# oven-controller-v1.net
KiCad netlist of a schematic drawn in EAGLE
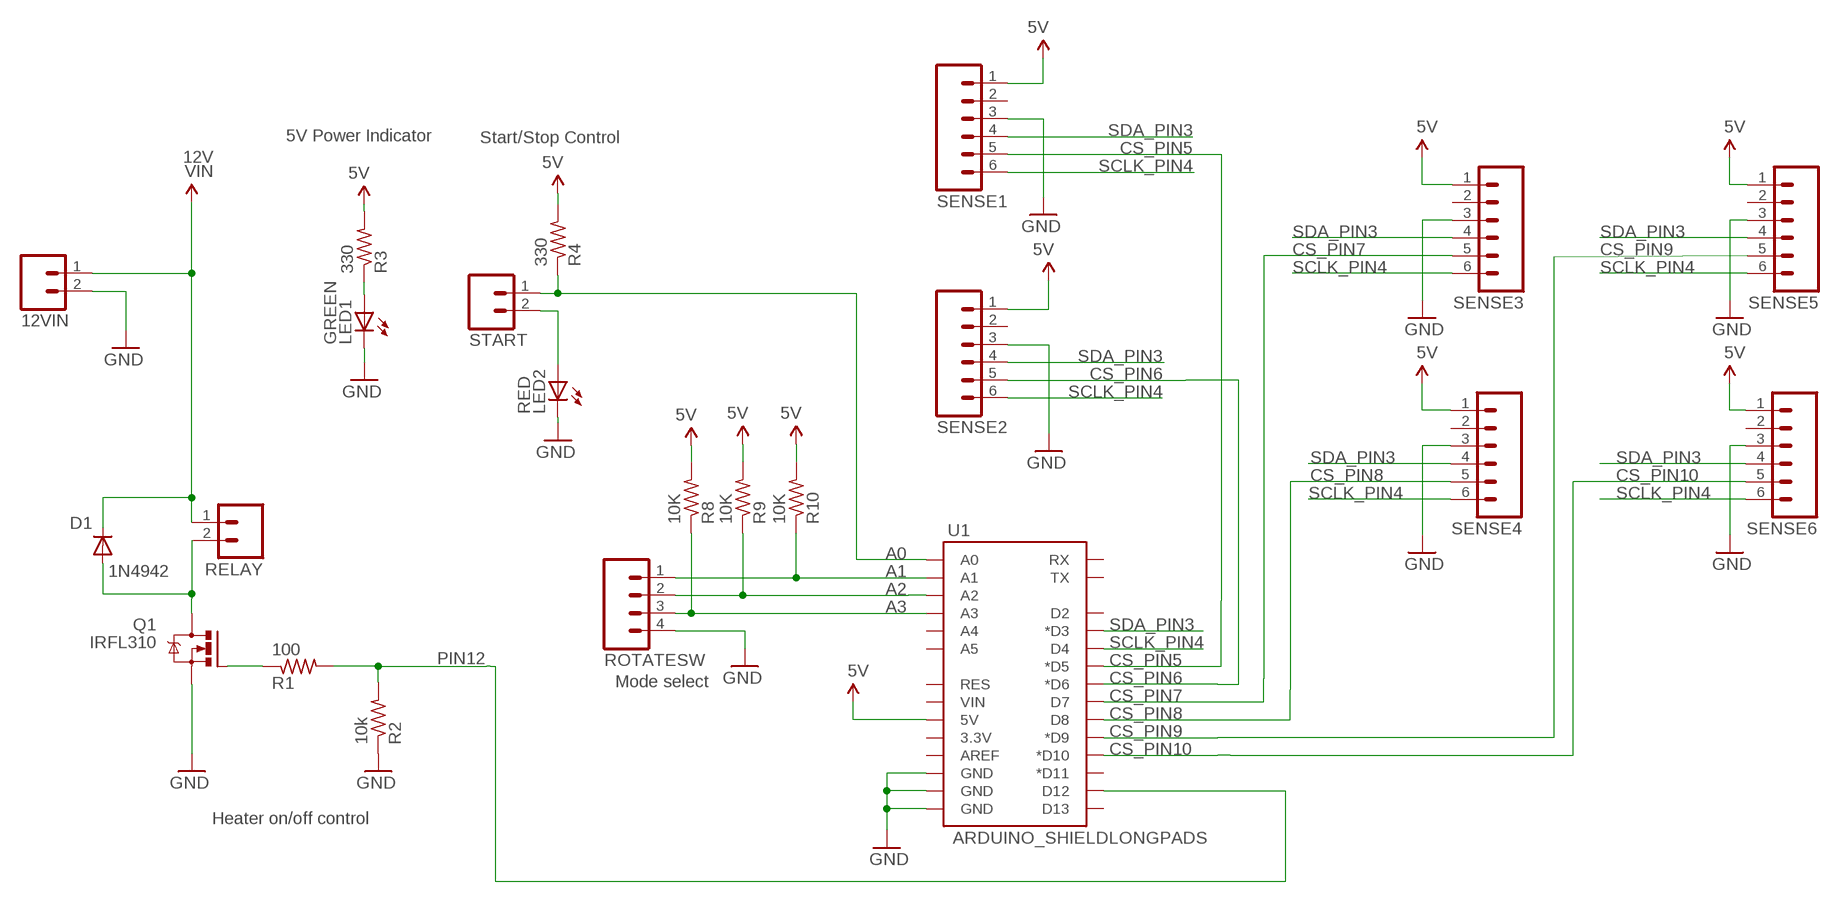
[diagram p0: schematic, sheet 1]

(export (version "E")
  (design (tool "Eeschema 10.0.6"))
  (components
    (comp (ref "12VIN")
      (value "M023.5MM_LOCK")
      (footprint "eagle-import:SCREWTERMINAL-3.5MM-2_LOCK")
      (libsource (lib "eagle-import") (part "M023.5MM_LOCK"))
    )
    (comp (ref "D1")
      (value "1N4942")
      (footprint "eagle-import:DO41-10")
      (libsource (lib "eagle-import") (part "1N4942"))
    )
    (comp (ref "LED1")
      (value "GREEN")
      (footprint "eagle-import:LED5MM")
      (libsource (lib "eagle-import") (part "LED5MM"))
    )
    (comp (ref "LED2")
      (value "RED")
      (footprint "eagle-import:LED5MM")
      (libsource (lib "eagle-import") (part "LED5MM"))
    )
    (comp (ref "Q1")
      (value "IRFL310")
      (footprint "eagle-import:TO220BV")
      (libsource (lib "eagle-import") (part "IRF520"))
    )
    (comp (ref "R1")
      (value "100")
      (footprint "eagle-import:V234_12")
      (libsource (lib "eagle-import") (part "R-US_V234/12"))
    )
    (comp (ref "R2")
      (value "10k")
      (footprint "eagle-import:V234_12")
      (libsource (lib "eagle-import") (part "R-US_V234/12"))
    )
    (comp (ref "R3")
      (value "330")
      (footprint "eagle-import:0207_10")
      (libsource (lib "eagle-import") (part "R-US_0207/10"))
    )
    (comp (ref "R4")
      (value "330")
      (footprint "eagle-import:0207_10")
      (libsource (lib "eagle-import") (part "R-US_0207/10"))
    )
    (comp (ref "R8")
      (value "10K")
      (footprint "eagle-import:0207_10")
      (libsource (lib "eagle-import") (part "R-US_0207/10"))
    )
    (comp (ref "R9")
      (value "10K")
      (footprint "eagle-import:0207_10")
      (libsource (lib "eagle-import") (part "R-US_0207/10"))
    )
    (comp (ref "R10")
      (value "10K")
      (footprint "eagle-import:0207_10")
      (libsource (lib "eagle-import") (part "R-US_0207/10"))
    )
    (comp (ref "RELAY")
      (value "M023.5MM_LOCK")
      (footprint "eagle-import:SCREWTERMINAL-3.5MM-2_LOCK")
      (libsource (lib "eagle-import") (part "M023.5MM_LOCK"))
    )
    (comp (ref "ROTATESW")
      (value "M04LOCK_LONGPADS")
      (footprint "eagle-import:1X04_LOCK_LONGPADS")
      (libsource (lib "eagle-import") (part "M04LOCK_LONGPADS"))
    )
    (comp (ref "SENSE1")
      (value "M06LOCK_LONGPADS")
      (footprint "eagle-import:1X06_LOCK_LONGPADS")
      (libsource (lib "eagle-import") (part "M06LOCK_LONGPADS"))
    )
    (comp (ref "SENSE2")
      (value "M06LOCK_LONGPADS")
      (footprint "eagle-import:1X06_LOCK_LONGPADS")
      (libsource (lib "eagle-import") (part "M06LOCK_LONGPADS"))
    )
    (comp (ref "SENSE3")
      (value "M06LOCK_LONGPADS")
      (footprint "eagle-import:1X06_LOCK_LONGPADS")
      (libsource (lib "eagle-import") (part "M06LOCK_LONGPADS"))
    )
    (comp (ref "SENSE4")
      (value "M06LOCK_LONGPADS")
      (footprint "eagle-import:1X06_LOCK_LONGPADS")
      (libsource (lib "eagle-import") (part "M06LOCK_LONGPADS"))
    )
    (comp (ref "SENSE5")
      (value "M06LOCK_LONGPADS")
      (footprint "eagle-import:1X06_LOCK_LONGPADS")
      (libsource (lib "eagle-import") (part "M06LOCK_LONGPADS"))
    )
    (comp (ref "SENSE6")
      (value "M06LOCK_LONGPADS")
      (footprint "eagle-import:1X06_LOCK_LONGPADS")
      (libsource (lib "eagle-import") (part "M06LOCK_LONGPADS"))
    )
    (comp (ref "START")
      (value "M023.5MM_LOCK")
      (footprint "eagle-import:SCREWTERMINAL-3.5MM-2_LOCK")
      (libsource (lib "eagle-import") (part "M023.5MM_LOCK"))
    )
    (comp (ref "U1")
      (value "ARDUINO_SHIELDLONGPADS")
      (footprint "eagle-import:DUEMILANOVE_SHIELD_LONGPADS")
      (libsource (lib "eagle-import") (part "ARDUINO_SHIELDLONGPADS"))
    )
  )
  (nets
    (net (code "1") (name "/A0") (class "Default")
      (node (ref "R4") (pin "1") (pinfunction "1_1") (pintype "passive"))
      (node (ref "START") (pin "1") (pinfunction "1_1") (pintype "passive"))
      (node (ref "U1") (pin "A0") (pinfunction "A0_A0") (pintype "bidirectional"))
    )
    (net (code "2") (name "/A1") (class "Default")
      (node (ref "R10") (pin "1") (pinfunction "1_1") (pintype "passive"))
      (node (ref "ROTATESW") (pin "1") (pinfunction "1_1") (pintype "passive"))
      (node (ref "U1") (pin "A1") (pinfunction "A1_A1") (pintype "bidirectional"))
    )
    (net (code "3") (name "/A2") (class "Default")
      (node (ref "R9") (pin "1") (pinfunction "1_1") (pintype "passive"))
      (node (ref "ROTATESW") (pin "2") (pinfunction "2_2") (pintype "passive"))
      (node (ref "U1") (pin "A2") (pinfunction "A2_A2") (pintype "bidirectional"))
    )
    (net (code "4") (name "/A3") (class "Default")
      (node (ref "R8") (pin "1") (pinfunction "1_1") (pintype "passive"))
      (node (ref "ROTATESW") (pin "3") (pinfunction "3_3") (pintype "passive"))
      (node (ref "U1") (pin "A3") (pinfunction "A3_A3") (pintype "bidirectional"))
    )
    (net (code "5") (name "/CS_PIN5") (class "Default")
      (node (ref "SENSE1") (pin "5") (pinfunction "5_5") (pintype "passive"))
      (node (ref "U1") (pin "D5") (pinfunction "*D5_D5") (pintype "bidirectional"))
    )
    (net (code "6") (name "/CS_PIN6") (class "Default")
      (node (ref "SENSE2") (pin "5") (pinfunction "5_5") (pintype "passive"))
      (node (ref "U1") (pin "D6") (pinfunction "*D6_D6") (pintype "bidirectional"))
    )
    (net (code "7") (name "/CS_PIN7") (class "Default")
      (node (ref "SENSE3") (pin "5") (pinfunction "5_5") (pintype "passive"))
      (node (ref "U1") (pin "D7") (pinfunction "D7_D7") (pintype "bidirectional"))
    )
    (net (code "8") (name "/CS_PIN8") (class "Default")
      (node (ref "SENSE4") (pin "5") (pinfunction "5_5") (pintype "passive"))
      (node (ref "U1") (pin "D8") (pinfunction "D8_D8") (pintype "bidirectional"))
    )
    (net (code "9") (name "/CS_PIN9") (class "Default")
      (node (ref "SENSE5") (pin "5") (pinfunction "5_5") (pintype "passive"))
      (node (ref "U1") (pin "D9") (pinfunction "*D9_D9") (pintype "bidirectional"))
    )
    (net (code "10") (name "/CS_PIN10") (class "Default")
      (node (ref "SENSE6") (pin "5") (pinfunction "5_5") (pintype "passive"))
      (node (ref "U1") (pin "D10") (pinfunction "*D10_D10") (pintype "bidirectional"))
    )
    (net (code "11") (name "/PIN12") (class "Default")
      (node (ref "R1") (pin "2") (pinfunction "2_2") (pintype "passive"))
      (node (ref "R2") (pin "2") (pinfunction "2_2") (pintype "passive"))
      (node (ref "U1") (pin "D12") (pinfunction "D12_D12") (pintype "bidirectional"))
    )
    (net (code "12") (name "/SCLK_PIN4") (class "Default")
      (node (ref "SENSE1") (pin "6") (pinfunction "6_6") (pintype "passive"))
      (node (ref "SENSE2") (pin "6") (pinfunction "6_6") (pintype "passive"))
      (node (ref "SENSE3") (pin "6") (pinfunction "6_6") (pintype "passive"))
      (node (ref "SENSE4") (pin "6") (pinfunction "6_6") (pintype "passive"))
      (node (ref "SENSE5") (pin "6") (pinfunction "6_6") (pintype "passive"))
      (node (ref "SENSE6") (pin "6") (pinfunction "6_6") (pintype "passive"))
      (node (ref "U1") (pin "D4") (pinfunction "D4_D4") (pintype "bidirectional"))
    )
    (net (code "13") (name "/SDA_PIN3") (class "Default")
      (node (ref "SENSE1") (pin "4") (pinfunction "4_4") (pintype "passive"))
      (node (ref "SENSE2") (pin "4") (pinfunction "4_4") (pintype "passive"))
      (node (ref "SENSE3") (pin "4") (pinfunction "4_4") (pintype "passive"))
      (node (ref "SENSE4") (pin "4") (pinfunction "4_4") (pintype "passive"))
      (node (ref "SENSE5") (pin "4") (pinfunction "4_4") (pintype "passive"))
      (node (ref "SENSE6") (pin "4") (pinfunction "4_4") (pintype "passive"))
      (node (ref "U1") (pin "D3") (pinfunction "*D3_D3") (pintype "bidirectional"))
    )
    (net (code "14") (name "5V") (class "Default")
      (node (ref "R10") (pin "2") (pinfunction "2_2") (pintype "passive"))
      (node (ref "R3") (pin "2") (pinfunction "2_2") (pintype "passive"))
      (node (ref "R4") (pin "2") (pinfunction "2_2") (pintype "passive"))
      (node (ref "R8") (pin "2") (pinfunction "2_2") (pintype "passive"))
      (node (ref "R9") (pin "2") (pinfunction "2_2") (pintype "passive"))
      (node (ref "SENSE1") (pin "1") (pinfunction "1_1") (pintype "passive"))
      (node (ref "SENSE2") (pin "1") (pinfunction "1_1") (pintype "passive"))
      (node (ref "SENSE3") (pin "1") (pinfunction "1_1") (pintype "passive"))
      (node (ref "SENSE4") (pin "1") (pinfunction "1_1") (pintype "passive"))
      (node (ref "SENSE5") (pin "1") (pinfunction "1_1") (pintype "passive"))
      (node (ref "SENSE6") (pin "1") (pinfunction "1_1") (pintype "passive"))
      (node (ref "U1") (pin "5V") (pinfunction "5V_5V") (pintype "bidirectional"))
    )
    (net (code "15") (name "GND") (class "Default")
      (node (ref "12VIN") (pin "2") (pinfunction "2_2") (pintype "passive"))
      (node (ref "LED1") (pin "K") (pinfunction "C_K") (pintype "passive"))
      (node (ref "LED2") (pin "K") (pinfunction "C_K") (pintype "passive"))
      (node (ref "Q1") (pin "S") (pinfunction "S_S") (pintype "passive"))
      (node (ref "R2") (pin "1") (pinfunction "1_1") (pintype "passive"))
      (node (ref "ROTATESW") (pin "4") (pinfunction "4_4") (pintype "passive"))
      (node (ref "SENSE1") (pin "3") (pinfunction "3_3") (pintype "passive"))
      (node (ref "SENSE2") (pin "3") (pinfunction "3_3") (pintype "passive"))
      (node (ref "SENSE3") (pin "3") (pinfunction "3_3") (pintype "passive"))
      (node (ref "SENSE4") (pin "3") (pinfunction "3_3") (pintype "passive"))
      (node (ref "SENSE5") (pin "3") (pinfunction "3_3") (pintype "passive"))
      (node (ref "SENSE6") (pin "3") (pinfunction "3_3") (pintype "passive"))
      (node (ref "U1") (pin "GND@0") (pinfunction "GND_GND@0") (pintype "bidirectional"))
      (node (ref "U1") (pin "GND@1") (pinfunction "GND_GND@1") (pintype "bidirectional"))
      (node (ref "U1") (pin "GND@2") (pinfunction "GND_GND@2") (pintype "bidirectional"))
    )
    (net (code "16") (name "Net-(D1-PadA)") (class "Default")
      (node (ref "D1") (pin "A") (pinfunction "A_A") (pintype "passive"))
      (node (ref "Q1") (pin "D") (pinfunction "D_D") (pintype "passive"))
      (node (ref "RELAY") (pin "2") (pinfunction "2_2") (pintype "passive"))
    )
    (net (code "17") (name "Net-(LED1-PadA)") (class "Default")
      (node (ref "LED1") (pin "A") (pinfunction "A_A") (pintype "passive"))
      (node (ref "R3") (pin "1") (pinfunction "1_1") (pintype "passive"))
    )
    (net (code "18") (name "Net-(LED2-PadA)") (class "Default")
      (node (ref "LED2") (pin "A") (pinfunction "A_A") (pintype "passive"))
      (node (ref "START") (pin "2") (pinfunction "2_2") (pintype "passive"))
    )
    (net (code "19") (name "Net-(Q1-PadG)") (class "Default")
      (node (ref "Q1") (pin "G") (pinfunction "G_G") (pintype "passive"))
      (node (ref "R1") (pin "1") (pinfunction "1_1") (pintype "passive"))
    )
    (net (code "20") (name "VIN") (class "Default")
      (node (ref "12VIN") (pin "1") (pinfunction "1_1") (pintype "passive"))
      (node (ref "D1") (pin "C") (pinfunction "C_C") (pintype "passive"))
      (node (ref "RELAY") (pin "1") (pinfunction "1_1") (pintype "passive"))
    )
    (net (code "21") (name "unconnected-(SENSE1-Pad2)") (class "Default")
      (node (ref "SENSE1") (pin "2") (pinfunction "2_2") (pintype "passive"))
    )
    (net (code "22") (name "unconnected-(SENSE2-Pad2)") (class "Default")
      (node (ref "SENSE2") (pin "2") (pinfunction "2_2") (pintype "passive"))
    )
    (net (code "23") (name "unconnected-(SENSE3-Pad2)") (class "Default")
      (node (ref "SENSE3") (pin "2") (pinfunction "2_2") (pintype "passive"))
    )
    (net (code "24") (name "unconnected-(SENSE4-Pad2)") (class "Default")
      (node (ref "SENSE4") (pin "2") (pinfunction "2_2") (pintype "passive"))
    )
    (net (code "25") (name "unconnected-(SENSE5-Pad2)") (class "Default")
      (node (ref "SENSE5") (pin "2") (pinfunction "2_2") (pintype "passive"))
    )
    (net (code "26") (name "unconnected-(SENSE6-Pad2)") (class "Default")
      (node (ref "SENSE6") (pin "2") (pinfunction "2_2") (pintype "passive"))
    )
    (net (code "27") (name "unconnected-(U1-*D11-PadD11)") (class "Default")
      (node (ref "U1") (pin "D11") (pinfunction "*D11_D11") (pintype "bidirectional"))
    )
    (net (code "28") (name "unconnected-(U1-Pad3.3V)") (class "Default")
      (node (ref "U1") (pin "3.3V") (pinfunction "3.3V_3.3V") (pintype "bidirectional"))
    )
    (net (code "29") (name "unconnected-(U1-PadA4)") (class "Default")
      (node (ref "U1") (pin "A4") (pinfunction "A4_A4") (pintype "bidirectional"))
    )
    (net (code "30") (name "unconnected-(U1-PadA5)") (class "Default")
      (node (ref "U1") (pin "A5") (pinfunction "A5_A5") (pintype "bidirectional"))
    )
    (net (code "31") (name "unconnected-(U1-PadAREF)") (class "Default")
      (node (ref "U1") (pin "AREF") (pinfunction "AREF_AREF") (pintype "bidirectional"))
    )
    (net (code "32") (name "unconnected-(U1-PadD2)") (class "Default")
      (node (ref "U1") (pin "D2") (pinfunction "D2_D2") (pintype "bidirectional"))
    )
    (net (code "33") (name "unconnected-(U1-PadD13)") (class "Default")
      (node (ref "U1") (pin "D13") (pinfunction "D13_D13") (pintype "bidirectional"))
    )
    (net (code "34") (name "unconnected-(U1-PadRES)") (class "Default")
      (node (ref "U1") (pin "RES") (pinfunction "RES_RES") (pintype "bidirectional"))
    )
    (net (code "35") (name "unconnected-(U1-PadRX)") (class "Default")
      (node (ref "U1") (pin "RX") (pinfunction "RX_RX") (pintype "bidirectional"))
    )
    (net (code "36") (name "unconnected-(U1-PadTX)") (class "Default")
      (node (ref "U1") (pin "TX") (pinfunction "TX_TX") (pintype "bidirectional"))
    )
    (net (code "37") (name "unconnected-(U1-PadVIN)") (class "Default")
      (node (ref "U1") (pin "VIN") (pinfunction "VIN_VIN") (pintype "bidirectional"))
    )
  )
)
